# LCD_Sheet.net
KiCad netlist of a schematic drawn in Altium Designer
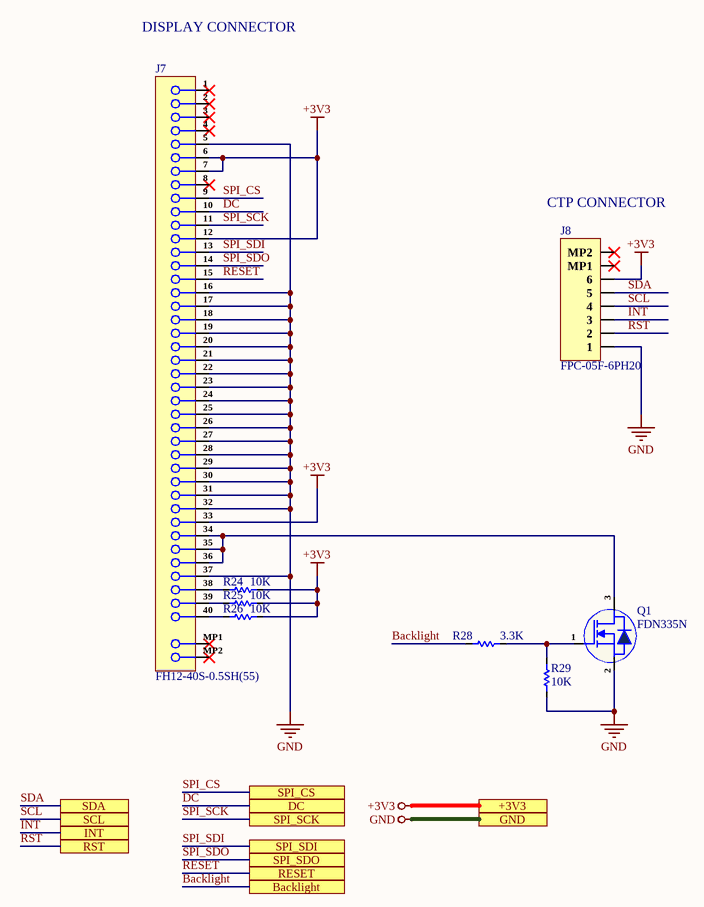
[diagram p0: LCD_Sheet.SchDoc]

(export (version "E")
  (design (tool "Eeschema 10.0.6"))
  (components
    (comp (ref "J7")
      (value "FH12-40S-0.5SH(55)")
      (footprint "FH12-40S-0.5SH(55)")
      (description "CONN FFC BOTTOM 40POS 0.50MM R/A")
      (fields (field (name "MANUFACTURER") "Hirose") (field (name "LCSC PART NUMBER") "C202114"))
      (libsource (lib "DigitalAzanClock") (part "FH12-40S-0.5SH(55)"))
    )
    (comp (ref "J8")
      (value "FPC-05F-6PH20")
      (footprint "FPC-05F-6PH20")
      (fields (field (name "MANUFACTURER") "XUNPU") (field (name "LCSC PART NUMBER") "C2856796"))
      (libsource (lib "DigitalAzanClock") (part "FPC-05F-6PH20"))
    )
    (comp (ref "Q1")
      (value "FDN335N")
      (footprint "SOT-23")
      (description "SOT-23 MOSFETs ROHS")
      (fields (field (name "MANUFACTURER") "TECH PUBLIC") (field (name "LCSC PART NUMBER") "C5123904"))
      (libsource (lib "DigitalAzanClock") (part "FDN335N"))
    )
    (comp (ref "R24")
      (value "10K")
      (footprint "Res-0603")
      (description "RES SMD 10K OHM 0.1% 1/10W 0603")
      (fields
        (field (name "MANUFACTURER") "Yageo")
        (field (name "MANUFACTURER PART NUMBER") "RT0603BRD0710KL")
      )
      (libsource (lib "DigitalAzanClock") (part "RT0603BRD0710KL"))
    )
    (comp (ref "R25")
      (value "10K")
      (footprint "Res-0603")
      (description "RES SMD 10K OHM 0.1% 1/10W 0603")
      (fields
        (field (name "MANUFACTURER") "Yageo")
        (field (name "MANUFACTURER PART NUMBER") "RT0603BRD0710KL")
      )
      (libsource (lib "DigitalAzanClock") (part "RT0603BRD0710KL"))
    )
    (comp (ref "R26")
      (value "10K")
      (footprint "Res-0603")
      (description "RES SMD 10K OHM 0.1% 1/10W 0603")
      (fields
        (field (name "MANUFACTURER") "Yageo")
        (field (name "MANUFACTURER PART NUMBER") "RT0603BRD0710KL")
      )
      (libsource (lib "DigitalAzanClock") (part "RT0603BRD0710KL"))
    )
    (comp (ref "R28")
      (value "3.3K")
      (footprint "Res-0603")
      (description "100mW Thick Film Resistors 75V ±100ppm/℃ ±1% 3.3kΩ 0603 Chip Resistor - Surface Mount ROHS")
      (fields
        (field (name "MANUFACTURER") "UNI-ROYAL(Uniroyal Elec)")
        (field (name "MANUFACTURER PART NUMBER") "0603WAF3301T5E")
      )
      (libsource (lib "DigitalAzanClock") (part "0603WAF3301T5E"))
    )
    (comp (ref "R29")
      (value "10K")
      (footprint "Res-0603")
      (description "RES SMD 10K OHM 0.1% 1/10W 0603")
      (fields
        (field (name "MANUFACTURER") "Yageo")
        (field (name "MANUFACTURER PART NUMBER") "RT0603BRD0710KL")
      )
      (libsource (lib "DigitalAzanClock") (part "RT0603BRD0710KL"))
    )
  )
  (nets
    (net (code "1") (name "+3V3") (class "Default")
      (node (ref "J7") (pin "12") (pinfunction "12_12") (pintype "passive"))
      (node (ref "J7") (pin "33") (pinfunction "33_33") (pintype "passive"))
      (node (ref "J7") (pin "6") (pinfunction "6_6") (pintype "passive"))
      (node (ref "J7") (pin "7") (pinfunction "7_7") (pintype "passive"))
      (node (ref "J8") (pin "6") (pinfunction "6_6") (pintype "passive"))
      (node (ref "R24") (pin "2") (pinfunction "2_2") (pintype "passive"))
      (node (ref "R25") (pin "2") (pinfunction "2_2") (pintype "passive"))
      (node (ref "R26") (pin "2") (pinfunction "2_2") (pintype "passive"))
    )
    (net (code "2") (name "/Backlight") (class "Default")
      (node (ref "R28") (pin "1") (pinfunction "1_1") (pintype "passive"))
    )
    (net (code "3") (name "/DC") (class "Default")
      (node (ref "J7") (pin "10") (pinfunction "10_10") (pintype "passive"))
    )
    (net (code "4") (name "/INT") (class "Default")
      (node (ref "J8") (pin "3") (pinfunction "3_3") (pintype "passive"))
    )
    (net (code "5") (name "/RESET") (class "Default")
      (node (ref "J7") (pin "15") (pinfunction "15_15") (pintype "passive"))
    )
    (net (code "6") (name "/RST") (class "Default")
      (node (ref "J8") (pin "2") (pinfunction "2_2") (pintype "passive"))
    )
    (net (code "7") (name "/SCL") (class "Default")
      (node (ref "J8") (pin "4") (pinfunction "4_4") (pintype "passive"))
    )
    (net (code "8") (name "/SDA") (class "Default")
      (node (ref "J8") (pin "5") (pinfunction "5_5") (pintype "passive"))
    )
    (net (code "9") (name "/SPI_CS") (class "Default")
      (node (ref "J7") (pin "9") (pinfunction "9_9") (pintype "passive"))
    )
    (net (code "10") (name "/SPI_SCK") (class "Default")
      (node (ref "J7") (pin "11") (pinfunction "11_11") (pintype "passive"))
    )
    (net (code "11") (name "/SPI_SDI") (class "Default")
      (node (ref "J7") (pin "13") (pinfunction "13_13") (pintype "passive"))
    )
    (net (code "12") (name "/SPI_SDO") (class "Default")
      (node (ref "J7") (pin "14") (pinfunction "14_14") (pintype "passive"))
    )
    (net (code "13") (name "GND") (class "Default")
      (node (ref "J7") (pin "16") (pinfunction "16_16") (pintype "passive"))
      (node (ref "J7") (pin "17") (pinfunction "17_17") (pintype "passive"))
      (node (ref "J7") (pin "18") (pinfunction "18_18") (pintype "passive"))
      (node (ref "J7") (pin "19") (pinfunction "19_19") (pintype "passive"))
      (node (ref "J7") (pin "20") (pinfunction "20_20") (pintype "passive"))
      (node (ref "J7") (pin "21") (pinfunction "21_21") (pintype "passive"))
      (node (ref "J7") (pin "22") (pinfunction "22_22") (pintype "passive"))
      (node (ref "J7") (pin "23") (pinfunction "23_23") (pintype "passive"))
      (node (ref "J7") (pin "24") (pinfunction "24_24") (pintype "passive"))
      (node (ref "J7") (pin "25") (pinfunction "25_25") (pintype "passive"))
      (node (ref "J7") (pin "26") (pinfunction "26_26") (pintype "passive"))
      (node (ref "J7") (pin "27") (pinfunction "27_27") (pintype "passive"))
      (node (ref "J7") (pin "28") (pinfunction "28_28") (pintype "passive"))
      (node (ref "J7") (pin "29") (pinfunction "29_29") (pintype "passive"))
      (node (ref "J7") (pin "30") (pinfunction "30_30") (pintype "passive"))
      (node (ref "J7") (pin "31") (pinfunction "31_31") (pintype "passive"))
      (node (ref "J7") (pin "32") (pinfunction "32_32") (pintype "passive"))
      (node (ref "J7") (pin "37") (pinfunction "37_37") (pintype "passive"))
      (node (ref "J7") (pin "5") (pinfunction "5_5") (pintype "passive"))
      (node (ref "J8") (pin "1") (pinfunction "1_1") (pintype "passive"))
      (node (ref "Q1") (pin "2") (pinfunction "S_2") (pintype "passive"))
      (node (ref "R29") (pin "1") (pinfunction "1_1") (pintype "passive"))
    )
    (net (code "14") (name "Net-(J7-Pad38)") (class "Default")
      (node (ref "J7") (pin "38") (pinfunction "38_38") (pintype "passive"))
      (node (ref "R24") (pin "1") (pinfunction "1_1") (pintype "passive"))
    )
    (net (code "15") (name "Net-(J7-Pad39)") (class "Default")
      (node (ref "J7") (pin "39") (pinfunction "39_39") (pintype "passive"))
      (node (ref "R25") (pin "1") (pinfunction "1_1") (pintype "passive"))
    )
    (net (code "16") (name "Net-(J7-Pad40)") (class "Default")
      (node (ref "J7") (pin "40") (pinfunction "40_40") (pintype "passive"))
      (node (ref "R26") (pin "1") (pinfunction "1_1") (pintype "passive"))
    )
    (net (code "17") (name "Net-(Q1-D)") (class "Default")
      (node (ref "J7") (pin "34") (pinfunction "34_34") (pintype "passive"))
      (node (ref "J7") (pin "35") (pinfunction "35_35") (pintype "passive"))
      (node (ref "J7") (pin "36") (pinfunction "36_36") (pintype "passive"))
      (node (ref "Q1") (pin "3") (pinfunction "D_3") (pintype "passive"))
    )
    (net (code "18") (name "Net-(Q1-G)") (class "Default")
      (node (ref "Q1") (pin "1") (pinfunction "G_1") (pintype "passive"))
      (node (ref "R28") (pin "2") (pinfunction "2_2") (pintype "passive"))
      (node (ref "R29") (pin "2") (pinfunction "2_2") (pintype "passive"))
    )
    (net (code "19") (name "unconnected-(J7-Pad1)") (class "Default")
      (node (ref "J7") (pin "1") (pinfunction "1_1") (pintype "passive+no_connect"))
    )
    (net (code "20") (name "unconnected-(J7-Pad2)") (class "Default")
      (node (ref "J7") (pin "2") (pinfunction "2_2") (pintype "passive+no_connect"))
    )
    (net (code "21") (name "unconnected-(J7-Pad3)") (class "Default")
      (node (ref "J7") (pin "3") (pinfunction "3_3") (pintype "passive+no_connect"))
    )
    (net (code "22") (name "unconnected-(J7-Pad4)") (class "Default")
      (node (ref "J7") (pin "4") (pinfunction "4_4") (pintype "passive+no_connect"))
    )
    (net (code "23") (name "unconnected-(J7-Pad8)") (class "Default")
      (node (ref "J7") (pin "8") (pinfunction "8_8") (pintype "passive+no_connect"))
    )
    (net (code "24") (name "unconnected-(J7-PadMP1)") (class "Default")
      (node (ref "J7") (pin "MP1") (pinfunction "MP1_MP1") (pintype "passive+no_connect"))
    )
    (net (code "25") (name "unconnected-(J7-PadMP2)") (class "Default")
      (node (ref "J7") (pin "MP2") (pinfunction "MP2_MP2") (pintype "passive+no_connect"))
    )
    (net (code "26") (name "unconnected-(J8-PadMP1)") (class "Default")
      (node (ref "J8") (pin "MP1") (pinfunction "MP1_MP1") (pintype "passive+no_connect"))
    )
    (net (code "27") (name "unconnected-(J8-PadMP2)") (class "Default")
      (node (ref "J8") (pin "MP2") (pinfunction "MP2_MP2") (pintype "passive+no_connect"))
    )
  )
)
